# NailUV_2x5x3.net
KiCad netlist of a schematic drawn in EAGLE
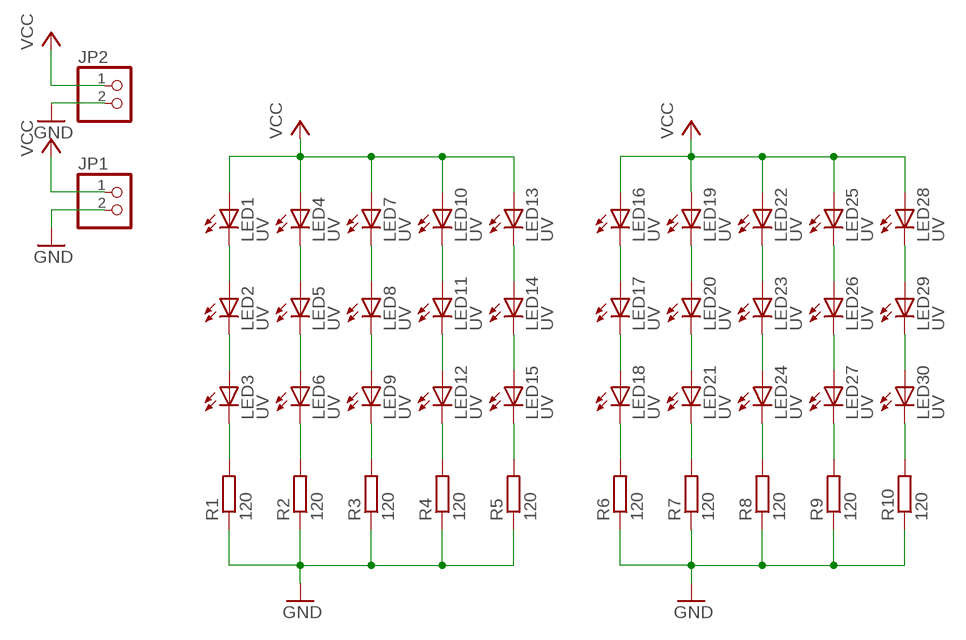
[diagram p0: schematic, sheet 1]

(export (version "E")
  (design (tool "Eeschema 10.0.6"))
  (components
    (comp (ref "JP1")
      (value "PINHD-1X2")
      (footprint "eagle-import:1X02")
      (libsource (lib "eagle-import") (part "PINHD-1X2"))
    )
    (comp (ref "JP2")
      (value "PINHD-1X2")
      (footprint "eagle-import:1X02")
      (libsource (lib "eagle-import") (part "PINHD-1X2"))
    )
    (comp (ref "LED1")
      (value "UV")
      (footprint "eagle-import:LED5MM")
      (libsource (lib "eagle-import") (part "LED5MM"))
    )
    (comp (ref "LED2")
      (value "UV")
      (footprint "eagle-import:LED5MM")
      (libsource (lib "eagle-import") (part "LED5MM"))
    )
    (comp (ref "LED3")
      (value "UV")
      (footprint "eagle-import:LED5MM")
      (libsource (lib "eagle-import") (part "LED5MM"))
    )
    (comp (ref "LED4")
      (value "UV")
      (footprint "eagle-import:LED5MM")
      (libsource (lib "eagle-import") (part "LED5MM"))
    )
    (comp (ref "LED5")
      (value "UV")
      (footprint "eagle-import:LED5MM")
      (libsource (lib "eagle-import") (part "LED5MM"))
    )
    (comp (ref "LED6")
      (value "UV")
      (footprint "eagle-import:LED5MM")
      (libsource (lib "eagle-import") (part "LED5MM"))
    )
    (comp (ref "LED7")
      (value "UV")
      (footprint "eagle-import:LED5MM")
      (libsource (lib "eagle-import") (part "LED5MM"))
    )
    (comp (ref "LED8")
      (value "UV")
      (footprint "eagle-import:LED5MM")
      (libsource (lib "eagle-import") (part "LED5MM"))
    )
    (comp (ref "LED9")
      (value "UV")
      (footprint "eagle-import:LED5MM")
      (libsource (lib "eagle-import") (part "LED5MM"))
    )
    (comp (ref "LED10")
      (value "UV")
      (footprint "eagle-import:LED5MM")
      (libsource (lib "eagle-import") (part "LED5MM"))
    )
    (comp (ref "LED11")
      (value "UV")
      (footprint "eagle-import:LED5MM")
      (libsource (lib "eagle-import") (part "LED5MM"))
    )
    (comp (ref "LED12")
      (value "UV")
      (footprint "eagle-import:LED5MM")
      (libsource (lib "eagle-import") (part "LED5MM"))
    )
    (comp (ref "LED13")
      (value "UV")
      (footprint "eagle-import:LED5MM")
      (libsource (lib "eagle-import") (part "LED5MM"))
    )
    (comp (ref "LED14")
      (value "UV")
      (footprint "eagle-import:LED5MM")
      (libsource (lib "eagle-import") (part "LED5MM"))
    )
    (comp (ref "LED15")
      (value "UV")
      (footprint "eagle-import:LED5MM")
      (libsource (lib "eagle-import") (part "LED5MM"))
    )
    (comp (ref "LED16")
      (value "UV")
      (footprint "eagle-import:LED5MM")
      (libsource (lib "eagle-import") (part "LED5MM"))
    )
    (comp (ref "LED17")
      (value "UV")
      (footprint "eagle-import:LED5MM")
      (libsource (lib "eagle-import") (part "LED5MM"))
    )
    (comp (ref "LED18")
      (value "UV")
      (footprint "eagle-import:LED5MM")
      (libsource (lib "eagle-import") (part "LED5MM"))
    )
    (comp (ref "LED19")
      (value "UV")
      (footprint "eagle-import:LED5MM")
      (libsource (lib "eagle-import") (part "LED5MM"))
    )
    (comp (ref "LED20")
      (value "UV")
      (footprint "eagle-import:LED5MM")
      (libsource (lib "eagle-import") (part "LED5MM"))
    )
    (comp (ref "LED21")
      (value "UV")
      (footprint "eagle-import:LED5MM")
      (libsource (lib "eagle-import") (part "LED5MM"))
    )
    (comp (ref "LED22")
      (value "UV")
      (footprint "eagle-import:LED5MM")
      (libsource (lib "eagle-import") (part "LED5MM"))
    )
    (comp (ref "LED23")
      (value "UV")
      (footprint "eagle-import:LED5MM")
      (libsource (lib "eagle-import") (part "LED5MM"))
    )
    (comp (ref "LED24")
      (value "UV")
      (footprint "eagle-import:LED5MM")
      (libsource (lib "eagle-import") (part "LED5MM"))
    )
    (comp (ref "LED25")
      (value "UV")
      (footprint "eagle-import:LED5MM")
      (libsource (lib "eagle-import") (part "LED5MM"))
    )
    (comp (ref "LED26")
      (value "UV")
      (footprint "eagle-import:LED5MM")
      (libsource (lib "eagle-import") (part "LED5MM"))
    )
    (comp (ref "LED27")
      (value "UV")
      (footprint "eagle-import:LED5MM")
      (libsource (lib "eagle-import") (part "LED5MM"))
    )
    (comp (ref "LED28")
      (value "UV")
      (footprint "eagle-import:LED5MM")
      (libsource (lib "eagle-import") (part "LED5MM"))
    )
    (comp (ref "LED29")
      (value "UV")
      (footprint "eagle-import:LED5MM")
      (libsource (lib "eagle-import") (part "LED5MM"))
    )
    (comp (ref "LED30")
      (value "UV")
      (footprint "eagle-import:LED5MM")
      (libsource (lib "eagle-import") (part "LED5MM"))
    )
    (comp (ref "R1")
      (value "120")
      (footprint "eagle-import:0207_10")
      (libsource (lib "eagle-import") (part "R-EU_0207/10"))
    )
    (comp (ref "R2")
      (value "120")
      (footprint "eagle-import:0207_10")
      (libsource (lib "eagle-import") (part "R-EU_0207/10"))
    )
    (comp (ref "R3")
      (value "120")
      (footprint "eagle-import:0207_10")
      (libsource (lib "eagle-import") (part "R-EU_0207/10"))
    )
    (comp (ref "R4")
      (value "120")
      (footprint "eagle-import:0207_10")
      (libsource (lib "eagle-import") (part "R-EU_0207/10"))
    )
    (comp (ref "R5")
      (value "120")
      (footprint "eagle-import:0207_10")
      (libsource (lib "eagle-import") (part "R-EU_0207/10"))
    )
    (comp (ref "R6")
      (value "120")
      (footprint "eagle-import:0207_10")
      (libsource (lib "eagle-import") (part "R-EU_0207/10"))
    )
    (comp (ref "R7")
      (value "120")
      (footprint "eagle-import:0207_10")
      (libsource (lib "eagle-import") (part "R-EU_0207/10"))
    )
    (comp (ref "R8")
      (value "120")
      (footprint "eagle-import:0207_10")
      (libsource (lib "eagle-import") (part "R-EU_0207/10"))
    )
    (comp (ref "R9")
      (value "120")
      (footprint "eagle-import:0207_10")
      (libsource (lib "eagle-import") (part "R-EU_0207/10"))
    )
    (comp (ref "R10")
      (value "120")
      (footprint "eagle-import:0207_10")
      (libsource (lib "eagle-import") (part "R-EU_0207/10"))
    )
  )
  (nets
    (net (code "1") (name "GND") (class "Default")
      (node (ref "JP1") (pin "2") (pinfunction "2_2") (pintype "passive"))
      (node (ref "JP2") (pin "2") (pinfunction "2_2") (pintype "passive"))
      (node (ref "R1") (pin "1") (pinfunction "1_1") (pintype "passive"))
      (node (ref "R10") (pin "1") (pinfunction "1_1") (pintype "passive"))
      (node (ref "R2") (pin "1") (pinfunction "1_1") (pintype "passive"))
      (node (ref "R3") (pin "1") (pinfunction "1_1") (pintype "passive"))
      (node (ref "R4") (pin "1") (pinfunction "1_1") (pintype "passive"))
      (node (ref "R5") (pin "1") (pinfunction "1_1") (pintype "passive"))
      (node (ref "R6") (pin "1") (pinfunction "1_1") (pintype "passive"))
      (node (ref "R7") (pin "1") (pinfunction "1_1") (pintype "passive"))
      (node (ref "R8") (pin "1") (pinfunction "1_1") (pintype "passive"))
      (node (ref "R9") (pin "1") (pinfunction "1_1") (pintype "passive"))
    )
    (net (code "2") (name "Net-(LED1-C)") (class "Default")
      (node (ref "LED1") (pin "K") (pinfunction "C_K") (pintype "passive"))
      (node (ref "LED2") (pin "A") (pinfunction "A_A") (pintype "passive"))
    )
    (net (code "3") (name "Net-(LED2-C)") (class "Default")
      (node (ref "LED2") (pin "K") (pinfunction "C_K") (pintype "passive"))
      (node (ref "LED3") (pin "A") (pinfunction "A_A") (pintype "passive"))
    )
    (net (code "4") (name "Net-(LED3-C)") (class "Default")
      (node (ref "LED3") (pin "K") (pinfunction "C_K") (pintype "passive"))
      (node (ref "R1") (pin "2") (pinfunction "2_2") (pintype "passive"))
    )
    (net (code "5") (name "Net-(LED4-C)") (class "Default")
      (node (ref "LED4") (pin "K") (pinfunction "C_K") (pintype "passive"))
      (node (ref "LED5") (pin "A") (pinfunction "A_A") (pintype "passive"))
    )
    (net (code "6") (name "Net-(LED5-C)") (class "Default")
      (node (ref "LED5") (pin "K") (pinfunction "C_K") (pintype "passive"))
      (node (ref "LED6") (pin "A") (pinfunction "A_A") (pintype "passive"))
    )
    (net (code "7") (name "Net-(LED6-C)") (class "Default")
      (node (ref "LED6") (pin "K") (pinfunction "C_K") (pintype "passive"))
      (node (ref "R2") (pin "2") (pinfunction "2_2") (pintype "passive"))
    )
    (net (code "8") (name "Net-(LED7-C)") (class "Default")
      (node (ref "LED7") (pin "K") (pinfunction "C_K") (pintype "passive"))
      (node (ref "LED8") (pin "A") (pinfunction "A_A") (pintype "passive"))
    )
    (net (code "9") (name "Net-(LED8-C)") (class "Default")
      (node (ref "LED8") (pin "K") (pinfunction "C_K") (pintype "passive"))
      (node (ref "LED9") (pin "A") (pinfunction "A_A") (pintype "passive"))
    )
    (net (code "10") (name "Net-(LED9-C)") (class "Default")
      (node (ref "LED9") (pin "K") (pinfunction "C_K") (pintype "passive"))
      (node (ref "R3") (pin "2") (pinfunction "2_2") (pintype "passive"))
    )
    (net (code "11") (name "Net-(LED10-C)") (class "Default")
      (node (ref "LED10") (pin "K") (pinfunction "C_K") (pintype "passive"))
      (node (ref "LED11") (pin "A") (pinfunction "A_A") (pintype "passive"))
    )
    (net (code "12") (name "Net-(LED11-C)") (class "Default")
      (node (ref "LED11") (pin "K") (pinfunction "C_K") (pintype "passive"))
      (node (ref "LED12") (pin "A") (pinfunction "A_A") (pintype "passive"))
    )
    (net (code "13") (name "Net-(LED12-C)") (class "Default")
      (node (ref "LED12") (pin "K") (pinfunction "C_K") (pintype "passive"))
      (node (ref "R4") (pin "2") (pinfunction "2_2") (pintype "passive"))
    )
    (net (code "14") (name "Net-(LED13-C)") (class "Default")
      (node (ref "LED13") (pin "K") (pinfunction "C_K") (pintype "passive"))
      (node (ref "LED14") (pin "A") (pinfunction "A_A") (pintype "passive"))
    )
    (net (code "15") (name "Net-(LED14-C)") (class "Default")
      (node (ref "LED14") (pin "K") (pinfunction "C_K") (pintype "passive"))
      (node (ref "LED15") (pin "A") (pinfunction "A_A") (pintype "passive"))
    )
    (net (code "16") (name "Net-(LED15-C)") (class "Default")
      (node (ref "LED15") (pin "K") (pinfunction "C_K") (pintype "passive"))
      (node (ref "R5") (pin "2") (pinfunction "2_2") (pintype "passive"))
    )
    (net (code "17") (name "Net-(LED16-C)") (class "Default")
      (node (ref "LED16") (pin "K") (pinfunction "C_K") (pintype "passive"))
      (node (ref "LED17") (pin "A") (pinfunction "A_A") (pintype "passive"))
    )
    (net (code "18") (name "Net-(LED17-C)") (class "Default")
      (node (ref "LED17") (pin "K") (pinfunction "C_K") (pintype "passive"))
      (node (ref "LED18") (pin "A") (pinfunction "A_A") (pintype "passive"))
    )
    (net (code "19") (name "Net-(LED18-C)") (class "Default")
      (node (ref "LED18") (pin "K") (pinfunction "C_K") (pintype "passive"))
      (node (ref "R6") (pin "2") (pinfunction "2_2") (pintype "passive"))
    )
    (net (code "20") (name "Net-(LED19-C)") (class "Default")
      (node (ref "LED19") (pin "K") (pinfunction "C_K") (pintype "passive"))
      (node (ref "LED20") (pin "A") (pinfunction "A_A") (pintype "passive"))
    )
    (net (code "21") (name "Net-(LED20-C)") (class "Default")
      (node (ref "LED20") (pin "K") (pinfunction "C_K") (pintype "passive"))
      (node (ref "LED21") (pin "A") (pinfunction "A_A") (pintype "passive"))
    )
    (net (code "22") (name "Net-(LED21-C)") (class "Default")
      (node (ref "LED21") (pin "K") (pinfunction "C_K") (pintype "passive"))
      (node (ref "R7") (pin "2") (pinfunction "2_2") (pintype "passive"))
    )
    (net (code "23") (name "Net-(LED22-C)") (class "Default")
      (node (ref "LED22") (pin "K") (pinfunction "C_K") (pintype "passive"))
      (node (ref "LED23") (pin "A") (pinfunction "A_A") (pintype "passive"))
    )
    (net (code "24") (name "Net-(LED23-C)") (class "Default")
      (node (ref "LED23") (pin "K") (pinfunction "C_K") (pintype "passive"))
      (node (ref "LED24") (pin "A") (pinfunction "A_A") (pintype "passive"))
    )
    (net (code "25") (name "Net-(LED24-C)") (class "Default")
      (node (ref "LED24") (pin "K") (pinfunction "C_K") (pintype "passive"))
      (node (ref "R8") (pin "2") (pinfunction "2_2") (pintype "passive"))
    )
    (net (code "26") (name "Net-(LED25-C)") (class "Default")
      (node (ref "LED25") (pin "K") (pinfunction "C_K") (pintype "passive"))
      (node (ref "LED26") (pin "A") (pinfunction "A_A") (pintype "passive"))
    )
    (net (code "27") (name "Net-(LED26-C)") (class "Default")
      (node (ref "LED26") (pin "K") (pinfunction "C_K") (pintype "passive"))
      (node (ref "LED27") (pin "A") (pinfunction "A_A") (pintype "passive"))
    )
    (net (code "28") (name "Net-(LED27-C)") (class "Default")
      (node (ref "LED27") (pin "K") (pinfunction "C_K") (pintype "passive"))
      (node (ref "R9") (pin "2") (pinfunction "2_2") (pintype "passive"))
    )
    (net (code "29") (name "Net-(LED28-C)") (class "Default")
      (node (ref "LED28") (pin "K") (pinfunction "C_K") (pintype "passive"))
      (node (ref "LED29") (pin "A") (pinfunction "A_A") (pintype "passive"))
    )
    (net (code "30") (name "Net-(LED29-C)") (class "Default")
      (node (ref "LED29") (pin "K") (pinfunction "C_K") (pintype "passive"))
      (node (ref "LED30") (pin "A") (pinfunction "A_A") (pintype "passive"))
    )
    (net (code "31") (name "Net-(LED30-C)") (class "Default")
      (node (ref "LED30") (pin "K") (pinfunction "C_K") (pintype "passive"))
      (node (ref "R10") (pin "2") (pinfunction "2_2") (pintype "passive"))
    )
    (net (code "32") (name "VCC") (class "Default")
      (node (ref "JP1") (pin "1") (pinfunction "1_1") (pintype "passive"))
      (node (ref "JP2") (pin "1") (pinfunction "1_1") (pintype "passive"))
      (node (ref "LED1") (pin "A") (pinfunction "A_A") (pintype "passive"))
      (node (ref "LED10") (pin "A") (pinfunction "A_A") (pintype "passive"))
      (node (ref "LED13") (pin "A") (pinfunction "A_A") (pintype "passive"))
      (node (ref "LED16") (pin "A") (pinfunction "A_A") (pintype "passive"))
      (node (ref "LED19") (pin "A") (pinfunction "A_A") (pintype "passive"))
      (node (ref "LED22") (pin "A") (pinfunction "A_A") (pintype "passive"))
      (node (ref "LED25") (pin "A") (pinfunction "A_A") (pintype "passive"))
      (node (ref "LED28") (pin "A") (pinfunction "A_A") (pintype "passive"))
      (node (ref "LED4") (pin "A") (pinfunction "A_A") (pintype "passive"))
      (node (ref "LED7") (pin "A") (pinfunction "A_A") (pintype "passive"))
    )
  )
)
